# RasPi-BplusHAT-3v3.net
KiCad netlist of a schematic drawn in EAGLE
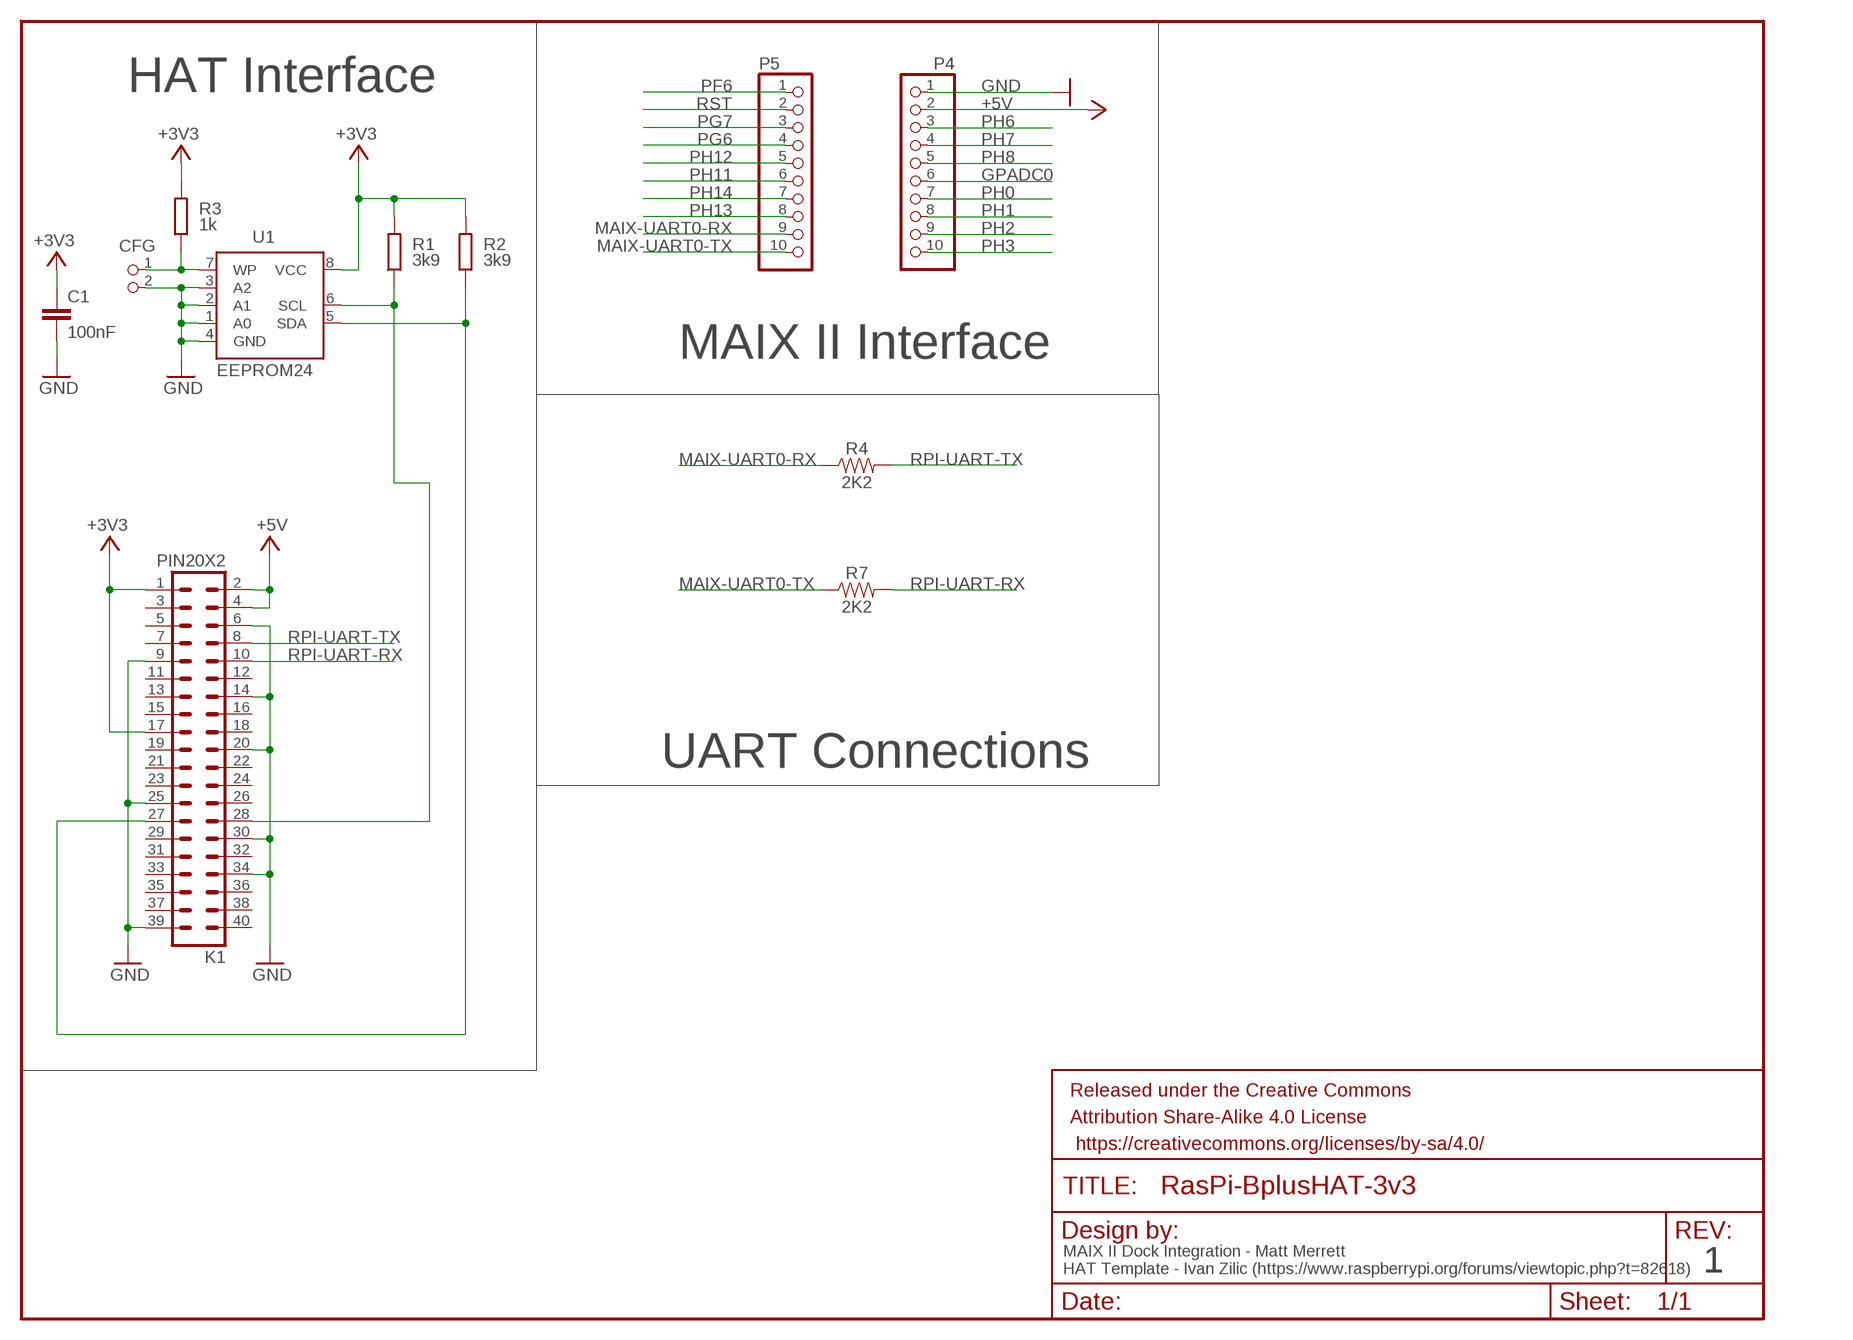
[diagram p0: schematic, sheet 1]

(export (version "E")
  (design (tool "Eeschema 10.0.6"))
  (components
    (comp (ref "C1")
      (value "100nF")
      (footprint "eagle-import:C0805K")
      (libsource (lib "eagle-import") (part "C-EUC0805K"))
    )
    (comp (ref "CFG")
      (value "PIN2_100")
      (footprint "eagle-import:PIN_W_2")
      (libsource (lib "eagle-import") (part "PIN2_100"))
    )
    (comp (ref "FRAME1")
      (value "FRAME-LETTER")
      (footprint "eagle-import:CREATIVE_COMMONS")
      (libsource (lib "eagle-import") (part "FRAME-LETTER"))
    )
    (comp (ref "K1")
      (value "PIN20X2")
      (footprint "eagle-import:PIN_20X2")
      (libsource (lib "eagle-import") (part "PIN20X2"))
    )
    (comp (ref "P4")
      (value "PINHD-1X10")
      (footprint "eagle-import:1X10")
      (libsource (lib "eagle-import") (part "PINHD-1X10"))
    )
    (comp (ref "P5")
      (value "PINHD-1X10")
      (footprint "eagle-import:1X10")
      (libsource (lib "eagle-import") (part "PINHD-1X10"))
    )
    (comp (ref "R1")
      (value "3k9")
      (footprint "eagle-import:M0805")
      (fields (field (name "TOLERANCE") "5%"))
      (libsource (lib "eagle-import") (part "R-EU_M0805"))
    )
    (comp (ref "R2")
      (value "3k9")
      (footprint "eagle-import:M0805")
      (fields (field (name "TOLERANCE") "5%"))
      (libsource (lib "eagle-import") (part "R-EU_M0805"))
    )
    (comp (ref "R3")
      (value "1k")
      (footprint "eagle-import:M0805")
      (fields (field (name "TOLERANCE") "5%"))
      (libsource (lib "eagle-import") (part "R-EU_M0805"))
    )
    (comp (ref "R4")
      (value "2K2")
      (footprint "eagle-import:AXIAL-0.3")
      (libsource (lib "eagle-import") (part "RESISTORAXIAL-0.3"))
    )
    (comp (ref "R7")
      (value "2K2")
      (footprint "eagle-import:AXIAL-0.3")
      (libsource (lib "eagle-import") (part "RESISTORAXIAL-0.3"))
    )
    (comp (ref "U1")
      (value "EEPROM24")
      (footprint "eagle-import:SOIC8")
      (libsource (lib "eagle-import") (part "EEPROM24"))
    )
  )
  (nets
    (net (code "1") (name "+3V3") (class "Default")
      (node (ref "C1") (pin "1") (pinfunction "1_1") (pintype "passive"))
      (node (ref "K1") (pin "1") (pinfunction "1_1") (pintype "passive"))
      (node (ref "K1") (pin "17") (pinfunction "17_17") (pintype "passive"))
      (node (ref "R1") (pin "2") (pinfunction "2_2") (pintype "passive"))
      (node (ref "R2") (pin "2") (pinfunction "2_2") (pintype "passive"))
      (node (ref "R3") (pin "2") (pinfunction "2_2") (pintype "passive"))
      (node (ref "U1") (pin "8") (pinfunction "VCC_8") (pintype "power_in"))
    )
    (net (code "2") (name "+5V") (class "Default")
      (node (ref "K1") (pin "2") (pinfunction "2_2") (pintype "passive"))
      (node (ref "K1") (pin "4") (pinfunction "4_4") (pintype "passive"))
      (node (ref "P4") (pin "2") (pinfunction "2_2") (pintype "passive"))
    )
    (net (code "3") (name "/GPADC0") (class "Default")
      (node (ref "P4") (pin "6") (pinfunction "6_6") (pintype "passive"))
    )
    (net (code "4") (name "/MAIX-UART0-RX") (class "Default")
      (node (ref "P5") (pin "9") (pinfunction "9_9") (pintype "passive"))
      (node (ref "R4") (pin "P$1") (pinfunction "1_P$1") (pintype "passive"))
    )
    (net (code "5") (name "/MAIX-UART0-TX") (class "Default")
      (node (ref "P5") (pin "10") (pinfunction "10_10") (pintype "passive"))
      (node (ref "R7") (pin "P$1") (pinfunction "1_P$1") (pintype "passive"))
    )
    (net (code "6") (name "/PF6") (class "Default")
      (node (ref "P5") (pin "1") (pinfunction "1_1") (pintype "passive"))
    )
    (net (code "7") (name "/PG6") (class "Default")
      (node (ref "P5") (pin "4") (pinfunction "4_4") (pintype "passive"))
    )
    (net (code "8") (name "/PG7") (class "Default")
      (node (ref "P5") (pin "3") (pinfunction "3_3") (pintype "passive"))
    )
    (net (code "9") (name "/PH0") (class "Default")
      (node (ref "P4") (pin "7") (pinfunction "7_7") (pintype "passive"))
    )
    (net (code "10") (name "/PH1") (class "Default")
      (node (ref "P4") (pin "8") (pinfunction "8_8") (pintype "passive"))
    )
    (net (code "11") (name "/PH2") (class "Default")
      (node (ref "P4") (pin "9") (pinfunction "9_9") (pintype "passive"))
    )
    (net (code "12") (name "/PH3") (class "Default")
      (node (ref "P4") (pin "10") (pinfunction "10_10") (pintype "passive"))
    )
    (net (code "13") (name "/PH6") (class "Default")
      (node (ref "P4") (pin "3") (pinfunction "3_3") (pintype "passive"))
    )
    (net (code "14") (name "/PH7") (class "Default")
      (node (ref "P4") (pin "4") (pinfunction "4_4") (pintype "passive"))
    )
    (net (code "15") (name "/PH8") (class "Default")
      (node (ref "P4") (pin "5") (pinfunction "5_5") (pintype "passive"))
    )
    (net (code "16") (name "/PH11") (class "Default")
      (node (ref "P5") (pin "6") (pinfunction "6_6") (pintype "passive"))
    )
    (net (code "17") (name "/PH12") (class "Default")
      (node (ref "P5") (pin "5") (pinfunction "5_5") (pintype "passive"))
    )
    (net (code "18") (name "/PH13") (class "Default")
      (node (ref "P5") (pin "8") (pinfunction "8_8") (pintype "passive"))
    )
    (net (code "19") (name "/PH14") (class "Default")
      (node (ref "P5") (pin "7") (pinfunction "7_7") (pintype "passive"))
    )
    (net (code "20") (name "/RPI-UART-RX") (class "Default")
      (node (ref "K1") (pin "10") (pinfunction "10_10") (pintype "passive"))
      (node (ref "R7") (pin "P$2") (pinfunction "2_P$2") (pintype "passive"))
    )
    (net (code "21") (name "/RPI-UART-TX") (class "Default")
      (node (ref "K1") (pin "8") (pinfunction "8_8") (pintype "passive"))
      (node (ref "R4") (pin "P$2") (pinfunction "2_P$2") (pintype "passive"))
    )
    (net (code "22") (name "/RST") (class "Default")
      (node (ref "P5") (pin "2") (pinfunction "2_2") (pintype "passive"))
    )
    (net (code "23") (name "GND") (class "Default")
      (node (ref "C1") (pin "2") (pinfunction "2_2") (pintype "passive"))
      (node (ref "CFG") (pin "2") (pinfunction "2_2") (pintype "passive"))
      (node (ref "K1") (pin "14") (pinfunction "14_14") (pintype "passive"))
      (node (ref "K1") (pin "20") (pinfunction "20_20") (pintype "passive"))
      (node (ref "K1") (pin "25") (pinfunction "25_25") (pintype "passive"))
      (node (ref "K1") (pin "30") (pinfunction "30_30") (pintype "passive"))
      (node (ref "K1") (pin "34") (pinfunction "34_34") (pintype "passive"))
      (node (ref "K1") (pin "39") (pinfunction "39_39") (pintype "passive"))
      (node (ref "K1") (pin "6") (pinfunction "6_6") (pintype "passive"))
      (node (ref "K1") (pin "9") (pinfunction "9_9") (pintype "passive"))
      (node (ref "P4") (pin "1") (pinfunction "1_1") (pintype "passive"))
      (node (ref "U1") (pin "1") (pinfunction "A0_1") (pintype "input"))
      (node (ref "U1") (pin "2") (pinfunction "A1_2") (pintype "input"))
      (node (ref "U1") (pin "3") (pinfunction "A2_3") (pintype "input"))
      (node (ref "U1") (pin "4") (pinfunction "GND_4") (pintype "power_in"))
    )
    (net (code "24") (name "Net-(U1-SCL)") (class "Default")
      (node (ref "K1") (pin "28") (pinfunction "28_28") (pintype "passive"))
      (node (ref "R1") (pin "1") (pinfunction "1_1") (pintype "passive"))
      (node (ref "U1") (pin "6") (pinfunction "SCL_6") (pintype "input"))
    )
    (net (code "25") (name "Net-(U1-SDA)") (class "Default")
      (node (ref "K1") (pin "27") (pinfunction "27_27") (pintype "passive"))
      (node (ref "R2") (pin "1") (pinfunction "1_1") (pintype "passive"))
      (node (ref "U1") (pin "5") (pinfunction "SDA_5") (pintype "bidirectional"))
    )
    (net (code "26") (name "Net-(U1-WP)") (class "Default")
      (node (ref "CFG") (pin "1") (pinfunction "1_1") (pintype "passive"))
      (node (ref "R3") (pin "1") (pinfunction "1_1") (pintype "passive"))
      (node (ref "U1") (pin "7") (pinfunction "WP_7") (pintype "input"))
    )
    (net (code "27") (name "unconnected-(K1-Pad3)") (class "Default")
      (node (ref "K1") (pin "3") (pinfunction "3_3") (pintype "passive"))
    )
    (net (code "28") (name "unconnected-(K1-Pad5)") (class "Default")
      (node (ref "K1") (pin "5") (pinfunction "5_5") (pintype "passive"))
    )
    (net (code "29") (name "unconnected-(K1-Pad7)") (class "Default")
      (node (ref "K1") (pin "7") (pinfunction "7_7") (pintype "passive"))
    )
    (net (code "30") (name "unconnected-(K1-Pad11)") (class "Default")
      (node (ref "K1") (pin "11") (pinfunction "11_11") (pintype "passive"))
    )
    (net (code "31") (name "unconnected-(K1-Pad12)") (class "Default")
      (node (ref "K1") (pin "12") (pinfunction "12_12") (pintype "passive"))
    )
    (net (code "32") (name "unconnected-(K1-Pad13)") (class "Default")
      (node (ref "K1") (pin "13") (pinfunction "13_13") (pintype "passive"))
    )
    (net (code "33") (name "unconnected-(K1-Pad15)") (class "Default")
      (node (ref "K1") (pin "15") (pinfunction "15_15") (pintype "passive"))
    )
    (net (code "34") (name "unconnected-(K1-Pad16)") (class "Default")
      (node (ref "K1") (pin "16") (pinfunction "16_16") (pintype "passive"))
    )
    (net (code "35") (name "unconnected-(K1-Pad18)") (class "Default")
      (node (ref "K1") (pin "18") (pinfunction "18_18") (pintype "passive"))
    )
    (net (code "36") (name "unconnected-(K1-Pad19)") (class "Default")
      (node (ref "K1") (pin "19") (pinfunction "19_19") (pintype "passive"))
    )
    (net (code "37") (name "unconnected-(K1-Pad21)") (class "Default")
      (node (ref "K1") (pin "21") (pinfunction "21_21") (pintype "passive"))
    )
    (net (code "38") (name "unconnected-(K1-Pad22)") (class "Default")
      (node (ref "K1") (pin "22") (pinfunction "22_22") (pintype "passive"))
    )
    (net (code "39") (name "unconnected-(K1-Pad23)") (class "Default")
      (node (ref "K1") (pin "23") (pinfunction "23_23") (pintype "passive"))
    )
    (net (code "40") (name "unconnected-(K1-Pad24)") (class "Default")
      (node (ref "K1") (pin "24") (pinfunction "24_24") (pintype "passive"))
    )
    (net (code "41") (name "unconnected-(K1-Pad26)") (class "Default")
      (node (ref "K1") (pin "26") (pinfunction "26_26") (pintype "passive"))
    )
    (net (code "42") (name "unconnected-(K1-Pad29)") (class "Default")
      (node (ref "K1") (pin "29") (pinfunction "29_29") (pintype "passive"))
    )
    (net (code "43") (name "unconnected-(K1-Pad31)") (class "Default")
      (node (ref "K1") (pin "31") (pinfunction "31_31") (pintype "passive"))
    )
    (net (code "44") (name "unconnected-(K1-Pad32)") (class "Default")
      (node (ref "K1") (pin "32") (pinfunction "32_32") (pintype "passive"))
    )
    (net (code "45") (name "unconnected-(K1-Pad33)") (class "Default")
      (node (ref "K1") (pin "33") (pinfunction "33_33") (pintype "passive"))
    )
    (net (code "46") (name "unconnected-(K1-Pad35)") (class "Default")
      (node (ref "K1") (pin "35") (pinfunction "35_35") (pintype "passive"))
    )
    (net (code "47") (name "unconnected-(K1-Pad36)") (class "Default")
      (node (ref "K1") (pin "36") (pinfunction "36_36") (pintype "passive"))
    )
    (net (code "48") (name "unconnected-(K1-Pad37)") (class "Default")
      (node (ref "K1") (pin "37") (pinfunction "37_37") (pintype "passive"))
    )
    (net (code "49") (name "unconnected-(K1-Pad38)") (class "Default")
      (node (ref "K1") (pin "38") (pinfunction "38_38") (pintype "passive"))
    )
    (net (code "50") (name "unconnected-(K1-Pad40)") (class "Default")
      (node (ref "K1") (pin "40") (pinfunction "40_40") (pintype "passive"))
    )
  )
)
